# eMMC_SD.net
KiCad netlist of a schematic drawn in Altium Designer
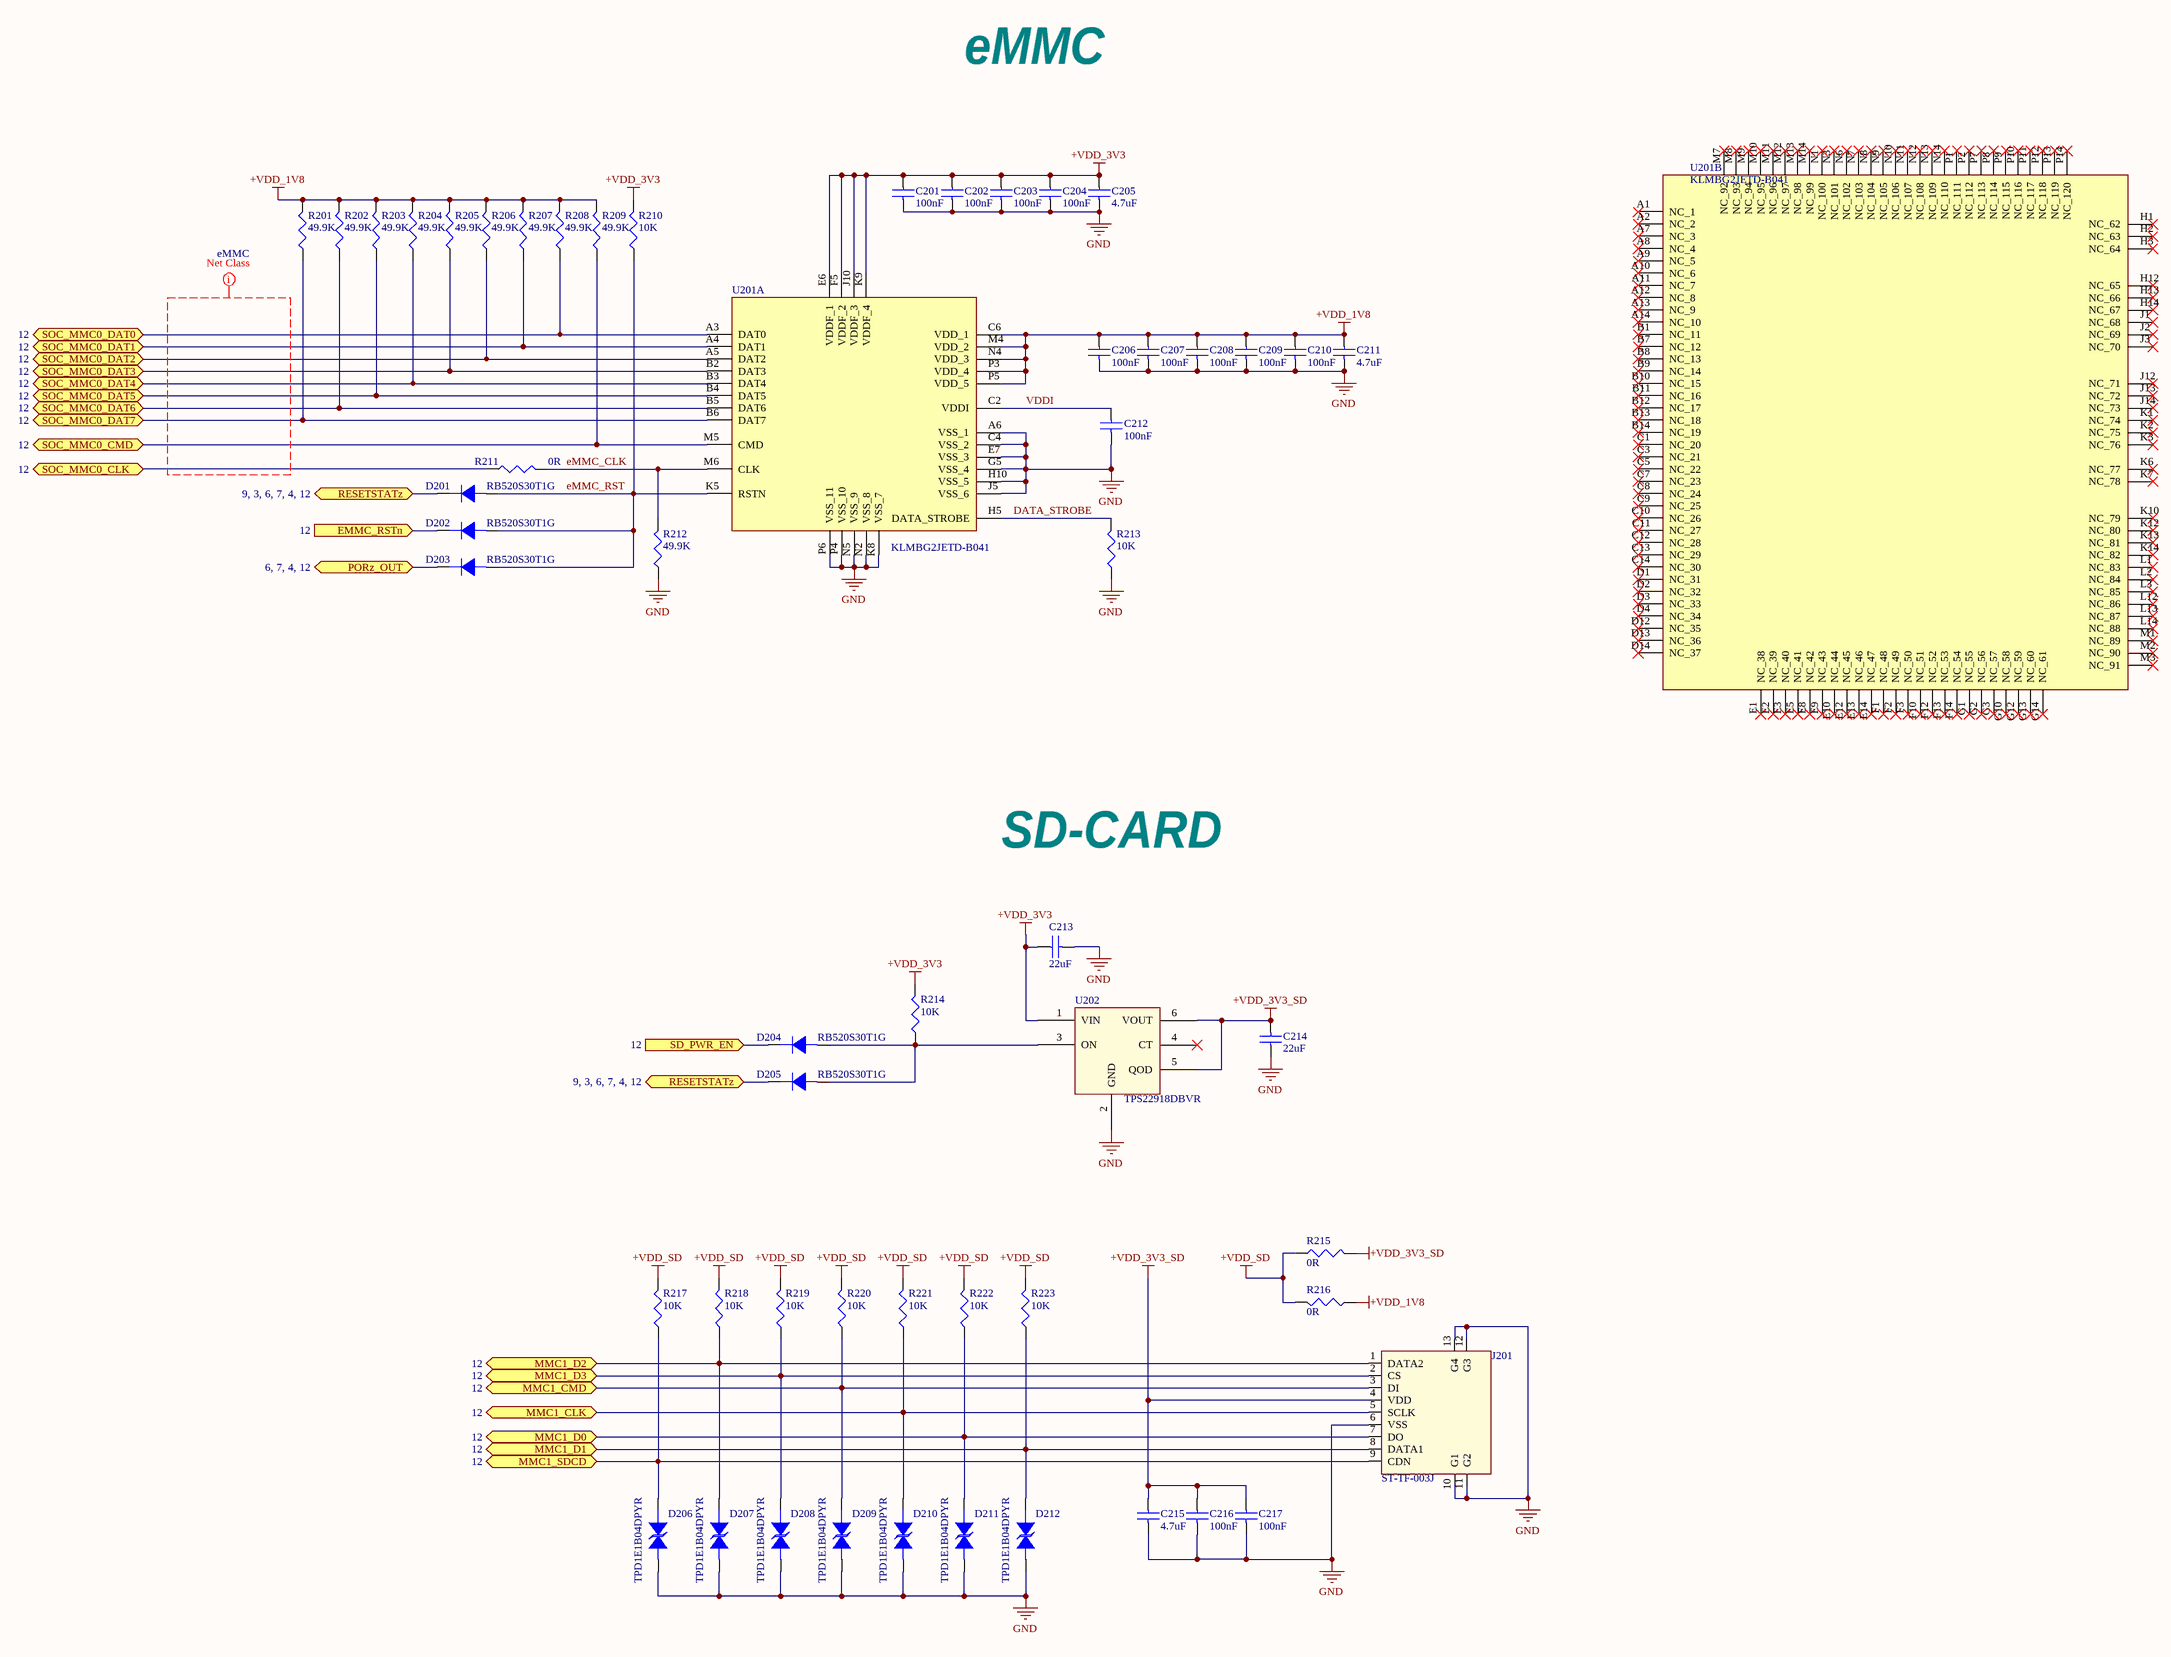
[diagram p0: eMMC&SD.SchDoc]

(export (version "E")
  (design (tool "Eeschema 10.0.6"))
  (components
    (comp (ref "C201")
      (value "100nF")
      (footprint "C0201")
      (description "Multilayer Ceramic Capacitor, 0.1 uF, 16 V, ± 10%, X5R, 0201 [0603 Metric]")
      (fields
        (field (name "MANUFACTURER") "Yageo")
        (field (name "MANUFACTURER PART NUMBER") "CC0201KRX5R6BB104")
      )
      (libsource (lib "Schlib SOM AM625") (part "CC0201KRX5R6BB104"))
    )
    (comp (ref "C202")
      (value "100nF")
      (footprint "C0201")
      (description "Multilayer Ceramic Capacitor, 0.1 uF, 16 V, ± 10%, X5R, 0201 [0603 Metric]")
      (fields
        (field (name "MANUFACTURER") "Yageo")
        (field (name "MANUFACTURER PART NUMBER") "CC0201KRX5R6BB104")
      )
      (libsource (lib "Schlib SOM AM625") (part "CC0201KRX5R6BB104"))
    )
    (comp (ref "C203")
      (value "100nF")
      (footprint "C0201")
      (description "Multilayer Ceramic Capacitor, 0.1 uF, 16 V, ± 10%, X5R, 0201 [0603 Metric]")
      (fields
        (field (name "MANUFACTURER") "Yageo")
        (field (name "MANUFACTURER PART NUMBER") "CC0201KRX5R6BB104")
      )
      (libsource (lib "Schlib SOM AM625") (part "CC0201KRX5R6BB104"))
    )
    (comp (ref "C204")
      (value "100nF")
      (footprint "C0201")
      (description "Multilayer Ceramic Capacitor, 0.1 uF, 16 V, ± 10%, X5R, 0201 [0603 Metric]")
      (fields
        (field (name "MANUFACTURER") "Yageo")
        (field (name "MANUFACTURER PART NUMBER") "CC0201KRX5R6BB104")
      )
      (libsource (lib "Schlib SOM AM625") (part "CC0201KRX5R6BB104"))
    )
    (comp (ref "C205")
      (value "4.7uF")
      (footprint "C0402")
      (description "Multilayer Ceramic Capacitor, 4.7 uF, 6.3V, ± 10%, X5R, 0402 [1005 Metric]")
      (fields
        (field (name "MANUFACTURER") "Yageo")
        (field (name "MANUFACTURER PART NUMBER") "CC0402MRX5R5BB475")
      )
      (libsource (lib "Schlib SOM AM625") (part "CC0402MRX5R5BB475"))
    )
    (comp (ref "C206")
      (value "100nF")
      (footprint "C0201")
      (description "Multilayer Ceramic Capacitor, 0.1 uF, 16 V, ± 10%, X5R, 0201 [0603 Metric]")
      (fields
        (field (name "MANUFACTURER") "Yageo")
        (field (name "MANUFACTURER PART NUMBER") "CC0201KRX5R6BB104")
      )
      (libsource (lib "Schlib SOM AM625") (part "CC0201KRX5R6BB104"))
    )
    (comp (ref "C207")
      (value "100nF")
      (footprint "C0201")
      (description "Multilayer Ceramic Capacitor, 0.1 uF, 16 V, ± 10%, X5R, 0201 [0603 Metric]")
      (fields
        (field (name "MANUFACTURER") "Yageo")
        (field (name "MANUFACTURER PART NUMBER") "CC0201KRX5R6BB104")
      )
      (libsource (lib "Schlib SOM AM625") (part "CC0201KRX5R6BB104"))
    )
    (comp (ref "C208")
      (value "100nF")
      (footprint "C0201")
      (description "Multilayer Ceramic Capacitor, 0.1 uF, 16 V, ± 10%, X5R, 0201 [0603 Metric]")
      (fields
        (field (name "MANUFACTURER") "Yageo")
        (field (name "MANUFACTURER PART NUMBER") "CC0201KRX5R6BB104")
      )
      (libsource (lib "Schlib SOM AM625") (part "CC0201KRX5R6BB104"))
    )
    (comp (ref "C209")
      (value "100nF")
      (footprint "C0201")
      (description "Multilayer Ceramic Capacitor, 0.1 uF, 16 V, ± 10%, X5R, 0201 [0603 Metric]")
      (fields
        (field (name "MANUFACTURER") "Yageo")
        (field (name "MANUFACTURER PART NUMBER") "CC0201KRX5R6BB104")
      )
      (libsource (lib "Schlib SOM AM625") (part "CC0201KRX5R6BB104"))
    )
    (comp (ref "C210")
      (value "100nF")
      (footprint "C0201")
      (description "Multilayer Ceramic Capacitor, 0.1 uF, 16 V, ± 10%, X5R, 0201 [0603 Metric]")
      (fields
        (field (name "MANUFACTURER") "Yageo")
        (field (name "MANUFACTURER PART NUMBER") "CC0201KRX5R6BB104")
      )
      (libsource (lib "Schlib SOM AM625") (part "CC0201KRX5R6BB104"))
    )
    (comp (ref "C211")
      (value "4.7uF")
      (footprint "C0402")
      (description "Multilayer Ceramic Capacitor, 4.7 uF, 6.3V, ± 10%, X5R, 0402 [1005 Metric]")
      (fields
        (field (name "MANUFACTURER") "Yageo")
        (field (name "MANUFACTURER PART NUMBER") "CC0402MRX5R5BB475")
      )
      (libsource (lib "Schlib SOM AM625") (part "CC0402MRX5R5BB475"))
    )
    (comp (ref "C212")
      (value "100nF")
      (footprint "C0201")
      (description "Multilayer Ceramic Capacitor, 0.1 uF, 16 V, ± 10%, X5R, 0201 [0603 Metric]")
      (fields
        (field (name "MANUFACTURER") "Yageo")
        (field (name "MANUFACTURER PART NUMBER") "CC0201KRX5R6BB104")
      )
      (libsource (lib "Schlib SOM AM625") (part "CC0201KRX5R6BB104"))
    )
    (comp (ref "C213")
      (value "22uF")
      (footprint "C0805")
      (description "Multilayer Ceramic Capacitor, 22 uF, 25 V, ± 20%, X6S, 0805 [2012 Metric]")
      (fields
        (field (name "MANUFACTURER") "Yageo")
        (field (name "MANUFACTURER PART NUMBER") "CC0805MKX5R8BB226")
      )
      (libsource (lib "Schlib SOM AM625") (part "CC0805MKX5R8BB226"))
    )
    (comp (ref "C214")
      (value "22uF")
      (footprint "C0805")
      (description "Multilayer Ceramic Capacitor, 22 uF, 25 V, ± 20%, X6S, 0805 [2012 Metric]")
      (fields
        (field (name "MANUFACTURER") "Yageo")
        (field (name "MANUFACTURER PART NUMBER") "CC0805MKX5R8BB226")
      )
      (libsource (lib "Schlib SOM AM625") (part "CC0805MKX5R8BB226"))
    )
    (comp (ref "C215")
      (value "4.7uF")
      (footprint "C0402")
      (description "Multilayer Ceramic Capacitor, 4.7 uF, 6.3V, ± 10%, X5R, 0402 [1005 Metric]")
      (fields
        (field (name "MANUFACTURER") "Yageo")
        (field (name "MANUFACTURER PART NUMBER") "CC0402MRX5R5BB475")
      )
      (libsource (lib "Schlib SOM AM625") (part "CC0402MRX5R5BB475"))
    )
    (comp (ref "C216")
      (value "100nF")
      (footprint "C0201")
      (description "Multilayer Ceramic Capacitor, 0.1 uF, 16 V, ± 10%, X5R, 0201 [0603 Metric]")
      (fields
        (field (name "MANUFACTURER") "Yageo")
        (field (name "MANUFACTURER PART NUMBER") "CC0201KRX5R6BB104")
      )
      (libsource (lib "Schlib SOM AM625") (part "CC0201KRX5R6BB104"))
    )
    (comp (ref "C217")
      (value "100nF")
      (footprint "C0201")
      (description "Multilayer Ceramic Capacitor, 0.1 uF, 16 V, ± 10%, X5R, 0201 [0603 Metric]")
      (fields
        (field (name "MANUFACTURER") "Yageo")
        (field (name "MANUFACTURER PART NUMBER") "CC0201KRX5R6BB104")
      )
      (libsource (lib "Schlib SOM AM625") (part "CC0201KRX5R6BB104"))
    )
    (comp (ref "D201")
      (value "RB520S30T1G")
      (footprint "sod_523")
      (description "Diode Schottky 30V 0.2A 2-Pin SOD-523 T/R - Product that comes on tape, but is not reeled")
      (fields (field (name "MANUFACTURER") "ON Semiconductor"))
      (libsource (lib "Schlib SOM AM625") (part "RB520S30T1G"))
    )
    (comp (ref "D202")
      (value "RB520S30T1G")
      (footprint "sod_523")
      (description "Diode Schottky 30V 0.2A 2-Pin SOD-523 T/R - Product that comes on tape, but is not reeled")
      (fields (field (name "MANUFACTURER") "ON Semiconductor"))
      (libsource (lib "Schlib SOM AM625") (part "RB520S30T1G"))
    )
    (comp (ref "D203")
      (value "RB520S30T1G")
      (footprint "sod_523")
      (description "Diode Schottky 30V 0.2A 2-Pin SOD-523 T/R - Product that comes on tape, but is not reeled")
      (fields (field (name "MANUFACTURER") "ON Semiconductor"))
      (libsource (lib "Schlib SOM AM625") (part "RB520S30T1G"))
    )
    (comp (ref "D204")
      (value "RB520S30T1G")
      (footprint "sod_523")
      (description "Diode Schottky 30V 0.2A 2-Pin SOD-523 T/R - Product that comes on tape, but is not reeled")
      (fields (field (name "MANUFACTURER") "ON Semiconductor"))
      (libsource (lib "Schlib SOM AM625") (part "RB520S30T1G"))
    )
    (comp (ref "D205")
      (value "RB520S30T1G")
      (footprint "sod_523")
      (description "Diode Schottky 30V 0.2A 2-Pin SOD-523 T/R - Product that comes on tape, but is not reeled")
      (fields (field (name "MANUFACTURER") "ON Semiconductor"))
      (libsource (lib "Schlib SOM AM625") (part "RB520S30T1G"))
    )
    (comp (ref "D206")
      (value "TPD1E1B04DPYR")
      (footprint "DIO_TPD1E05U06DPYR")
      (description "1-pF, ±3.6-V, ±30-kV ESD protection diode with 6-A 8/20-uS surge & Low Clamping in 0402 package")
      (fields (field (name "MANUFACTURER") "Texas Instruments"))
      (libsource (lib "Schlib SOM AM625") (part "TPD1E1B04DPYR"))
    )
    (comp (ref "D207")
      (value "TPD1E1B04DPYR")
      (footprint "DIO_TPD1E05U06DPYR")
      (description "1-pF, ±3.6-V, ±30-kV ESD protection diode with 6-A 8/20-uS surge & Low Clamping in 0402 package")
      (fields (field (name "MANUFACTURER") "Texas Instruments"))
      (libsource (lib "Schlib SOM AM625") (part "TPD1E1B04DPYR"))
    )
    (comp (ref "D208")
      (value "TPD1E1B04DPYR")
      (footprint "DIO_TPD1E05U06DPYR")
      (description "1-pF, ±3.6-V, ±30-kV ESD protection diode with 6-A 8/20-uS surge & Low Clamping in 0402 package")
      (fields (field (name "MANUFACTURER") "Texas Instruments"))
      (libsource (lib "Schlib SOM AM625") (part "TPD1E1B04DPYR"))
    )
    (comp (ref "D209")
      (value "TPD1E1B04DPYR")
      (footprint "DIO_TPD1E05U06DPYR")
      (description "1-pF, ±3.6-V, ±30-kV ESD protection diode with 6-A 8/20-uS surge & Low Clamping in 0402 package")
      (fields (field (name "MANUFACTURER") "Texas Instruments"))
      (libsource (lib "Schlib SOM AM625") (part "TPD1E1B04DPYR"))
    )
    (comp (ref "D210")
      (value "TPD1E1B04DPYR")
      (footprint "DIO_TPD1E05U06DPYR")
      (description "1-pF, ±3.6-V, ±30-kV ESD protection diode with 6-A 8/20-uS surge & Low Clamping in 0402 package")
      (fields (field (name "MANUFACTURER") "Texas Instruments"))
      (libsource (lib "Schlib SOM AM625") (part "TPD1E1B04DPYR"))
    )
    (comp (ref "D211")
      (value "TPD1E1B04DPYR")
      (footprint "DIO_TPD1E05U06DPYR")
      (description "1-pF, ±3.6-V, ±30-kV ESD protection diode with 6-A 8/20-uS surge & Low Clamping in 0402 package")
      (fields (field (name "MANUFACTURER") "Texas Instruments"))
      (libsource (lib "Schlib SOM AM625") (part "TPD1E1B04DPYR"))
    )
    (comp (ref "D212")
      (value "TPD1E1B04DPYR")
      (footprint "DIO_TPD1E05U06DPYR")
      (description "1-pF, ±3.6-V, ±30-kV ESD protection diode with 6-A 8/20-uS surge & Low Clamping in 0402 package")
      (fields (field (name "MANUFACTURER") "Texas Instruments"))
      (libsource (lib "Schlib SOM AM625") (part "TPD1E1B04DPYR"))
    )
    (comp (ref "J201")
      (value "ST-TF-003J")
      (footprint "SUNTECH_ST-TF-003A")
      (description "Conn Micro SD Card HDR 8 POS 1.1mm Solder RA SMD Embossed T/R 0.5A")
      (fields (field (name "MANUFACTURER") "Suntech"))
      (libsource (lib "Schlib SOM AM625") (part "ST-TF-003J"))
    )
    (comp (ref "R201")
      (value "49.9K")
      (footprint "R0402")
      (description "SMD Chip Resistor, 49.9 kOhm, ± 1%, 63 mW, 0402 [1005 Metric], Thick Film, General Purpose")
      (fields
        (field (name "MANUFACTURER") "Yageo")
        (field (name "MANUFACTURER PART NUMBER") "RC0402FR-0749K9L")
      )
      (libsource (lib "Schlib SOM AM625") (part "RC0402FR-0749K9L"))
    )
    (comp (ref "R202")
      (value "49.9K")
      (footprint "R0402")
      (description "SMD Chip Resistor, 49.9 kOhm, ± 1%, 63 mW, 0402 [1005 Metric], Thick Film, General Purpose")
      (fields
        (field (name "MANUFACTURER") "Yageo")
        (field (name "MANUFACTURER PART NUMBER") "RC0402FR-0749K9L")
      )
      (libsource (lib "Schlib SOM AM625") (part "RC0402FR-0749K9L"))
    )
    (comp (ref "R203")
      (value "49.9K")
      (footprint "R0402")
      (description "SMD Chip Resistor, 49.9 kOhm, ± 1%, 63 mW, 0402 [1005 Metric], Thick Film, General Purpose")
      (fields
        (field (name "MANUFACTURER") "Yageo")
        (field (name "MANUFACTURER PART NUMBER") "RC0402FR-0749K9L")
      )
      (libsource (lib "Schlib SOM AM625") (part "RC0402FR-0749K9L"))
    )
    (comp (ref "R204")
      (value "49.9K")
      (footprint "R0402")
      (description "SMD Chip Resistor, 49.9 kOhm, ± 1%, 63 mW, 0402 [1005 Metric], Thick Film, General Purpose")
      (fields
        (field (name "MANUFACTURER") "Yageo")
        (field (name "MANUFACTURER PART NUMBER") "RC0402FR-0749K9L")
      )
      (libsource (lib "Schlib SOM AM625") (part "RC0402FR-0749K9L"))
    )
    (comp (ref "R205")
      (value "49.9K")
      (footprint "R0402")
      (description "SMD Chip Resistor, 49.9 kOhm, ± 1%, 63 mW, 0402 [1005 Metric], Thick Film, General Purpose")
      (fields
        (field (name "MANUFACTURER") "Yageo")
        (field (name "MANUFACTURER PART NUMBER") "RC0402FR-0749K9L")
      )
      (libsource (lib "Schlib SOM AM625") (part "RC0402FR-0749K9L"))
    )
    (comp (ref "R206")
      (value "49.9K")
      (footprint "R0402")
      (description "SMD Chip Resistor, 49.9 kOhm, ± 1%, 63 mW, 0402 [1005 Metric], Thick Film, General Purpose")
      (fields
        (field (name "MANUFACTURER") "Yageo")
        (field (name "MANUFACTURER PART NUMBER") "RC0402FR-0749K9L")
      )
      (libsource (lib "Schlib SOM AM625") (part "RC0402FR-0749K9L"))
    )
    (comp (ref "R207")
      (value "49.9K")
      (footprint "R0402")
      (description "SMD Chip Resistor, 49.9 kOhm, ± 1%, 63 mW, 0402 [1005 Metric], Thick Film, General Purpose")
      (fields
        (field (name "MANUFACTURER") "Yageo")
        (field (name "MANUFACTURER PART NUMBER") "RC0402FR-0749K9L")
      )
      (libsource (lib "Schlib SOM AM625") (part "RC0402FR-0749K9L"))
    )
    (comp (ref "R208")
      (value "49.9K")
      (footprint "R0402")
      (description "SMD Chip Resistor, 49.9 kOhm, ± 1%, 63 mW, 0402 [1005 Metric], Thick Film, General Purpose")
      (fields
        (field (name "MANUFACTURER") "Yageo")
        (field (name "MANUFACTURER PART NUMBER") "RC0402FR-0749K9L")
      )
      (libsource (lib "Schlib SOM AM625") (part "RC0402FR-0749K9L"))
    )
    (comp (ref "R209")
      (value "49.9K")
      (footprint "R0402")
      (description "SMD Chip Resistor, 49.9 kOhm, ± 1%, 63 mW, 0402 [1005 Metric], Thick Film, General Purpose")
      (fields
        (field (name "MANUFACTURER") "Yageo")
        (field (name "MANUFACTURER PART NUMBER") "RC0402FR-0749K9L")
      )
      (libsource (lib "Schlib SOM AM625") (part "RC0402FR-0749K9L"))
    )
    (comp (ref "R210")
      (value "10K")
      (footprint "R0402")
      (description "RES 10.0K OHM 1/16W 1% 0402 SMD")
      (fields
        (field (name "MANUFACTURER") "Yageo")
        (field (name "MANUFACTURER PART NUMBER") "RC0402FR-0710KL")
      )
      (libsource (lib "Schlib SOM AM625") (part "RC0402FR-0710KL"))
    )
    (comp (ref "R211")
      (value "0R")
      (footprint "R0402")
      (description "Zero Ohm Resistor, Jumper, 0402 [1005 Metric], Thick Film, 63 mW, 1 A, Surface Mount")
      (fields
        (field (name "MANUFACTURER") "Yageo")
        (field (name "MANUFACTURER PART NUMBER") "RC0402JR-070RL")
      )
      (libsource (lib "Schlib SOM AM625") (part "RC0402JR-070RL"))
    )
    (comp (ref "R212")
      (value "49.9K")
      (footprint "R0402")
      (description "SMD Chip Resistor, 49.9 kOhm, ± 1%, 63 mW, 0402 [1005 Metric], Thick Film, General Purpose")
      (fields
        (field (name "MANUFACTURER") "Yageo")
        (field (name "MANUFACTURER PART NUMBER") "RC0402FR-0749K9L")
      )
      (libsource (lib "Schlib SOM AM625") (part "RC0402FR-0749K9L"))
    )
    (comp (ref "R213")
      (value "10K")
      (footprint "R0402")
      (description "RES 10.0K OHM 1/16W 1% 0402 SMD")
      (fields
        (field (name "MANUFACTURER") "Yageo")
        (field (name "MANUFACTURER PART NUMBER") "RC0402FR-0710KL")
      )
      (libsource (lib "Schlib SOM AM625") (part "RC0402FR-0710KL"))
    )
    (comp (ref "R214")
      (value "10K")
      (footprint "R0402")
      (description "RES 10.0K OHM 1/16W 1% 0402 SMD")
      (fields
        (field (name "MANUFACTURER") "Yageo")
        (field (name "MANUFACTURER PART NUMBER") "RC0402FR-0710KL")
      )
      (libsource (lib "Schlib SOM AM625") (part "RC0402FR-0710KL"))
    )
    (comp (ref "R215")
      (value "0R")
      (footprint "R0402")
      (description "Zero Ohm Resistor, Jumper, 0402 [1005 Metric], Thick Film, 63 mW, 1 A, Surface Mount")
      (fields
        (field (name "MANUFACTURER") "Yageo")
        (field (name "MANUFACTURER PART NUMBER") "RC0402JR-070RL")
      )
      (libsource (lib "Schlib SOM AM625") (part "RC0402JR-070RL"))
    )
    (comp (ref "R216")
      (value "0R")
      (footprint "R0402")
      (description "Zero Ohm Resistor, Jumper, 0402 [1005 Metric], Thick Film, 63 mW, 1 A, Surface Mount")
      (fields
        (field (name "MANUFACTURER") "Yageo")
        (field (name "MANUFACTURER PART NUMBER") "RC0402JR-070RL")
      )
      (libsource (lib "Schlib SOM AM625") (part "RC0402JR-070RL"))
    )
    (comp (ref "R217")
      (value "10K")
      (footprint "R0402")
      (description "RES 10.0K OHM 1/16W 1% 0402 SMD")
      (fields
        (field (name "MANUFACTURER") "Yageo")
        (field (name "MANUFACTURER PART NUMBER") "RC0402FR-0710KL")
      )
      (libsource (lib "Schlib SOM AM625") (part "RC0402FR-0710KL"))
    )
    (comp (ref "R218")
      (value "10K")
      (footprint "R0402")
      (description "RES 10.0K OHM 1/16W 1% 0402 SMD")
      (fields
        (field (name "MANUFACTURER") "Yageo")
        (field (name "MANUFACTURER PART NUMBER") "RC0402FR-0710KL")
      )
      (libsource (lib "Schlib SOM AM625") (part "RC0402FR-0710KL"))
    )
    (comp (ref "R219")
      (value "10K")
      (footprint "R0402")
      (description "RES 10.0K OHM 1/16W 1% 0402 SMD")
      (fields
        (field (name "MANUFACTURER") "Yageo")
        (field (name "MANUFACTURER PART NUMBER") "RC0402FR-0710KL")
      )
      (libsource (lib "Schlib SOM AM625") (part "RC0402FR-0710KL"))
    )
    (comp (ref "R220")
      (value "10K")
      (footprint "R0402")
      (description "RES 10.0K OHM 1/16W 1% 0402 SMD")
      (fields
        (field (name "MANUFACTURER") "Yageo")
        (field (name "MANUFACTURER PART NUMBER") "RC0402FR-0710KL")
      )
      (libsource (lib "Schlib SOM AM625") (part "RC0402FR-0710KL"))
    )
    (comp (ref "R221")
      (value "10K")
      (footprint "R0402")
      (description "RES 10.0K OHM 1/16W 1% 0402 SMD")
      (fields
        (field (name "MANUFACTURER") "Yageo")
        (field (name "MANUFACTURER PART NUMBER") "RC0402FR-0710KL")
      )
      (libsource (lib "Schlib SOM AM625") (part "RC0402FR-0710KL"))
    )
    (comp (ref "R222")
      (value "10K")
      (footprint "R0402")
      (description "RES 10.0K OHM 1/16W 1% 0402 SMD")
      (fields
        (field (name "MANUFACTURER") "Yageo")
        (field (name "MANUFACTURER PART NUMBER") "RC0402FR-0710KL")
      )
      (libsource (lib "Schlib SOM AM625") (part "RC0402FR-0710KL"))
    )
    (comp (ref "R223")
      (value "10K")
      (footprint "R0402")
      (description "RES 10.0K OHM 1/16W 1% 0402 SMD")
      (fields
        (field (name "MANUFACTURER") "Yageo")
        (field (name "MANUFACTURER PART NUMBER") "RC0402FR-0710KL")
      )
      (libsource (lib "Schlib SOM AM625") (part "RC0402FR-0710KL"))
    )
    (comp (ref "U201")
      (value "KLMBG2JETD-B041")
      (footprint "BGA153C50P14X14_1150X1300X80")
      (description "eMMC 5.1 BGA-153 eMMC ROHS")
      (libsource (lib "Schlib1") (part "KLMAG1JETD-B041"))
    )
    (comp (ref "U202")
      (value "TPS22918DBVR")
      (footprint "SOT23-6")
      (description "IC SINGLE CHANNEL LOAD SWITCH")
      (fields (field (name "MANUFACTURER") "Texas Instruments"))
      (libsource (lib "Schlib SOM AM625") (part "TPS22918DBVR"))
    )
  )
  (nets
    (net (code "1") (name "+VDD_1V8") (class "Default")
      (node (ref "C206") (pin "1") (pinfunction "1_1") (pintype "passive"))
      (node (ref "C207") (pin "1") (pinfunction "1_1") (pintype "passive"))
      (node (ref "C208") (pin "1") (pinfunction "1_1") (pintype "passive"))
      (node (ref "C209") (pin "1") (pinfunction "1_1") (pintype "passive"))
      (node (ref "C210") (pin "1") (pinfunction "1_1") (pintype "passive"))
      (node (ref "C211") (pin "1") (pinfunction "1_1") (pintype "passive"))
      (node (ref "R201") (pin "2") (pinfunction "2_2") (pintype "passive"))
      (node (ref "R202") (pin "2") (pinfunction "2_2") (pintype "passive"))
      (node (ref "R203") (pin "2") (pinfunction "2_2") (pintype "passive"))
      (node (ref "R204") (pin "2") (pinfunction "2_2") (pintype "passive"))
      (node (ref "R205") (pin "2") (pinfunction "2_2") (pintype "passive"))
      (node (ref "R206") (pin "2") (pinfunction "2_2") (pintype "passive"))
      (node (ref "R207") (pin "2") (pinfunction "2_2") (pintype "passive"))
      (node (ref "R208") (pin "2") (pinfunction "2_2") (pintype "passive"))
      (node (ref "R209") (pin "2") (pinfunction "2_2") (pintype "passive"))
      (node (ref "R216") (pin "1") (pinfunction "1_1") (pintype "passive"))
      (node (ref "U201") (pin "C6") (pinfunction "VDD_1_C6") (pintype "passive"))
      (node (ref "U201") (pin "M4") (pinfunction "VDD_2_M4") (pintype "passive"))
      (node (ref "U201") (pin "N4") (pinfunction "VDD_3_N4") (pintype "passive"))
      (node (ref "U201") (pin "P3") (pinfunction "VDD_4_P3") (pintype "passive"))
      (node (ref "U201") (pin "P5") (pinfunction "VDD_5_P5") (pintype "passive"))
    )
    (net (code "2") (name "+VDD_3V3") (class "Default")
      (node (ref "C201") (pin "1") (pinfunction "1_1") (pintype "passive"))
      (node (ref "C202") (pin "1") (pinfunction "1_1") (pintype "passive"))
      (node (ref "C203") (pin "1") (pinfunction "1_1") (pintype "passive"))
      (node (ref "C204") (pin "1") (pinfunction "1_1") (pintype "passive"))
      (node (ref "C205") (pin "1") (pinfunction "1_1") (pintype "passive"))
      (node (ref "C213") (pin "1") (pinfunction "1_1") (pintype "passive"))
      (node (ref "R210") (pin "2") (pinfunction "2_2") (pintype "passive"))
      (node (ref "R214") (pin "2") (pinfunction "2_2") (pintype "passive"))
      (node (ref "U201") (pin "E6") (pinfunction "VDDF_1_E6") (pintype "passive"))
      (node (ref "U201") (pin "F5") (pinfunction "VDDF_2_F5") (pintype "passive"))
      (node (ref "U201") (pin "J10") (pinfunction "VDDF_3_J10") (pintype "passive"))
      (node (ref "U201") (pin "K9") (pinfunction "VDDF_4_K9") (pintype "passive"))
      (node (ref "U202") (pin "1") (pinfunction "VIN_1") (pintype "passive"))
    )
    (net (code "3") (name "+VDD_3V3_SD") (class "Default")
      (node (ref "C214") (pin "2") (pinfunction "2_2") (pintype "passive"))
      (node (ref "C215") (pin "1") (pinfunction "1_1") (pintype "passive"))
      (node (ref "C216") (pin "1") (pinfunction "1_1") (pintype "passive"))
      (node (ref "C217") (pin "1") (pinfunction "1_1") (pintype "passive"))
      (node (ref "J201") (pin "4") (pinfunction "VDD_4") (pintype "passive"))
      (node (ref "R215") (pin "2") (pinfunction "2_2") (pintype "passive"))
      (node (ref "U202") (pin "5") (pinfunction "QOD_5") (pintype "passive"))
      (node (ref "U202") (pin "6") (pinfunction "VOUT_6") (pintype "passive"))
    )
    (net (code "4") (name "+VDD_SD") (class "Default")
      (node (ref "R215") (pin "1") (pinfunction "1_1") (pintype "passive"))
      (node (ref "R216") (pin "2") (pinfunction "2_2") (pintype "passive"))
      (node (ref "R217") (pin "2") (pinfunction "2_2") (pintype "passive"))
      (node (ref "R218") (pin "2") (pinfunction "2_2") (pintype "passive"))
      (node (ref "R219") (pin "2") (pinfunction "2_2") (pintype "passive"))
      (node (ref "R220") (pin "2") (pinfunction "2_2") (pintype "passive"))
      (node (ref "R221") (pin "2") (pinfunction "2_2") (pintype "passive"))
      (node (ref "R222") (pin "2") (pinfunction "2_2") (pintype "passive"))
      (node (ref "R223") (pin "2") (pinfunction "2_2") (pintype "passive"))
    )
    (net (code "5") (name "/DATA_STROBE") (class "Default")
      (node (ref "R213") (pin "2") (pinfunction "2_2") (pintype "passive"))
      (node (ref "U201") (pin "H5") (pinfunction "DATA_STROBE_H5") (pintype "passive"))
    )
    (net (code "6") (name "/EMMC_RSTn") (class "Default")
      (node (ref "D202") (pin "2") (pinfunction "C_2") (pintype "passive"))
    )
    (net (code "7") (name "/MMC1_CLK") (class "Default")
      (node (ref "D210") (pin "2") (pinfunction "2_2") (pintype "passive"))
      (node (ref "J201") (pin "5") (pinfunction "SCLK_5") (pintype "passive"))
      (node (ref "R221") (pin "1") (pinfunction "1_1") (pintype "passive"))
    )
    (net (code "8") (name "/MMC1_CMD") (class "Default")
      (node (ref "D209") (pin "2") (pinfunction "2_2") (pintype "passive"))
      (node (ref "J201") (pin "3") (pinfunction "DI_3") (pintype "passive"))
      (node (ref "R220") (pin "1") (pinfunction "1_1") (pintype "passive"))
    )
    (net (code "9") (name "/MMC1_D0") (class "Default")
      (node (ref "D211") (pin "2") (pinfunction "2_2") (pintype "passive"))
      (node (ref "J201") (pin "7") (pinfunction "DO_7") (pintype "passive"))
      (node (ref "R222") (pin "1") (pinfunction "1_1") (pintype "passive"))
    )
    (net (code "10") (name "/MMC1_D1") (class "Default")
      (node (ref "D212") (pin "2") (pinfunction "2_2") (pintype "passive"))
      (node (ref "J201") (pin "8") (pinfunction "DATA1_8") (pintype "passive"))
      (node (ref "R223") (pin "1") (pinfunction "1_1") (pintype "passive"))
    )
    (net (code "11") (name "/MMC1_D2") (class "Default")
      (node (ref "D207") (pin "2") (pinfunction "2_2") (pintype "passive"))
      (node (ref "J201") (pin "1") (pinfunction "DATA2_1") (pintype "passive"))
      (node (ref "R218") (pin "1") (pinfunction "1_1") (pintype "passive"))
    )
    (net (code "12") (name "/MMC1_D3") (class "Default")
      (node (ref "D208") (pin "2") (pinfunction "2_2") (pintype "passive"))
      (node (ref "J201") (pin "2") (pinfunction "CS_2") (pintype "passive"))
      (node (ref "R219") (pin "1") (pinfunction "1_1") (pintype "passive"))
    )
    (net (code "13") (name "/MMC1_SDCD") (class "Default")
      (node (ref "D206") (pin "2") (pinfunction "2_2") (pintype "passive"))
      (node (ref "J201") (pin "9") (pinfunction "CDN_9") (pintype "passive"))
      (node (ref "R217") (pin "1") (pinfunction "1_1") (pintype "passive"))
    )
    (net (code "14") (name "/PORz_OUT") (class "Default")
      (node (ref "D203") (pin "2") (pinfunction "C_2") (pintype "passive"))
    )
    (net (code "15") (name "/RESETSTATz") (class "Default")
      (node (ref "D201") (pin "2") (pinfunction "C_2") (pintype "passive"))
      (node (ref "D205") (pin "2") (pinfunction "C_2") (pintype "passive"))
    )
    (net (code "16") (name "/SD_PWR_EN") (class "Default")
      (node (ref "D204") (pin "2") (pinfunction "C_2") (pintype "passive"))
    )
    (net (code "17") (name "/SOC_MMC0_CLK") (class "Default")
      (node (ref "R211") (pin "1") (pinfunction "1_1") (pintype "passive"))
    )
    (net (code "18") (name "/SOC_MMC0_CMD") (class "Default")
      (node (ref "R209") (pin "1") (pinfunction "1_1") (pintype "passive"))
      (node (ref "U201") (pin "M5") (pinfunction "CMD_M5") (pintype "passive"))
    )
    (net (code "19") (name "/SOC_MMC0_DAT0") (class "Default")
      (node (ref "R208") (pin "1") (pinfunction "1_1") (pintype "passive"))
      (node (ref "U201") (pin "A3") (pinfunction "DAT0_A3") (pintype "passive"))
    )
    (net (code "20") (name "/SOC_MMC0_DAT1") (class "Default")
      (node (ref "R207") (pin "1") (pinfunction "1_1") (pintype "passive"))
      (node (ref "U201") (pin "A4") (pinfunction "DAT1_A4") (pintype "passive"))
    )
    (net (code "21") (name "/SOC_MMC0_DAT2") (class "Default")
      (node (ref "R206") (pin "1") (pinfunction "1_1") (pintype "passive"))
      (node (ref "U201") (pin "A5") (pinfunction "DAT2_A5") (pintype "passive"))
    )
    (net (code "22") (name "/SOC_MMC0_DAT3") (class "Default")
      (node (ref "R205") (pin "1") (pinfunction "1_1") (pintype "passive"))
      (node (ref "U201") (pin "B2") (pinfunction "DAT3_B2") (pintype "passive"))
    )
    (net (code "23") (name "/SOC_MMC0_DAT4") (class "Default")
      (node (ref "R204") (pin "1") (pinfunction "1_1") (pintype "passive"))
      (node (ref "U201") (pin "B3") (pinfunction "DAT4_B3") (pintype "passive"))
    )
    (net (code "24") (name "/SOC_MMC0_DAT5") (class "Default")
      (node (ref "R203") (pin "1") (pinfunction "1_1") (pintype "passive"))
      (node (ref "U201") (pin "B4") (pinfunction "DAT5_B4") (pintype "passive"))
    )
    (net (code "25") (name "/SOC_MMC0_DAT6") (class "Default")
      (node (ref "R202") (pin "1") (pinfunction "1_1") (pintype "passive"))
      (node (ref "U201") (pin "B5") (pinfunction "DAT6_B5") (pintype "passive"))
    )
    (net (code "26") (name "/SOC_MMC0_DAT7") (class "Default")
      (node (ref "R201") (pin "1") (pinfunction "1_1") (pintype "passive"))
      (node (ref "U201") (pin "B6") (pinfunction "DAT7_B6") (pintype "passive"))
    )
    (net (code "27") (name "/VDDI") (class "Default")
      (node (ref "C212") (pin "1") (pinfunction "1_1") (pintype "passive"))
      (node (ref "U201") (pin "C2") (pinfunction "VDDI_C2") (pintype "passive"))
    )
    (net (code "28") (name "/eMMC_CLK") (class "Default")
      (node (ref "R211") (pin "2") (pinfunction "2_2") (pintype "passive"))
      (node (ref "R212") (pin "2") (pinfunction "2_2") (pintype "passive"))
      (node (ref "U201") (pin "M6") (pinfunction "CLK_M6") (pintype "passive"))
    )
    (net (code "29") (name "/eMMC_RST") (class "Default")
      (node (ref "D201") (pin "1") (pinfunction "A_1") (pintype "passive"))
      (node (ref "D202") (pin "1") (pinfunction "A_1") (pintype "passive"))
      (node (ref "D203") (pin "1") (pinfunction "A_1") (pintype "passive"))
      (node (ref "R210") (pin "1") (pinfunction "1_1") (pintype "passive"))
      (node (ref "U201") (pin "K5") (pinfunction "RSTN_K5") (pintype "passive"))
    )
    (net (code "30") (name "GND") (class "Default")
      (node (ref "C201") (pin "2") (pinfunction "2_2") (pintype "passive"))
      (node (ref "C202") (pin "2") (pinfunction "2_2") (pintype "passive"))
      (node (ref "C203") (pin "2") (pinfunction "2_2") (pintype "passive"))
      (node (ref "C204") (pin "2") (pinfunction "2_2") (pintype "passive"))
      (node (ref "C205") (pin "2") (pinfunction "2_2") (pintype "passive"))
      (node (ref "C206") (pin "2") (pinfunction "2_2") (pintype "passive"))
      (node (ref "C207") (pin "2") (pinfunction "2_2") (pintype "passive"))
      (node (ref "C208") (pin "2") (pinfunction "2_2") (pintype "passive"))
      (node (ref "C209") (pin "2") (pinfunction "2_2") (pintype "passive"))
      (node (ref "C210") (pin "2") (pinfunction "2_2") (pintype "passive"))
      (node (ref "C211") (pin "2") (pinfunction "2_2") (pintype "passive"))
      (node (ref "C212") (pin "2") (pinfunction "2_2") (pintype "passive"))
      (node (ref "C213") (pin "2") (pinfunction "2_2") (pintype "passive"))
      (node (ref "C214") (pin "1") (pinfunction "1_1") (pintype "passive"))
      (node (ref "C215") (pin "2") (pinfunction "2_2") (pintype "passive"))
      (node (ref "C216") (pin "2") (pinfunction "2_2") (pintype "passive"))
      (node (ref "C217") (pin "2") (pinfunction "2_2") (pintype "passive"))
      (node (ref "D206") (pin "1") (pinfunction "1_1") (pintype "passive"))
      (node (ref "D207") (pin "1") (pinfunction "1_1") (pintype "passive"))
      (node (ref "D208") (pin "1") (pinfunction "1_1") (pintype "passive"))
      (node (ref "D209") (pin "1") (pinfunction "1_1") (pintype "passive"))
      (node (ref "D210") (pin "1") (pinfunction "1_1") (pintype "passive"))
      (node (ref "D211") (pin "1") (pinfunction "1_1") (pintype "passive"))
      (node (ref "D212") (pin "1") (pinfunction "1_1") (pintype "passive"))
      (node (ref "J201") (pin "10") (pinfunction "G1_10") (pintype "passive"))
      (node (ref "J201") (pin "11") (pinfunction "G2_11") (pintype "passive"))
      (node (ref "J201") (pin "12") (pinfunction "G3_12") (pintype "passive"))
      (node (ref "J201") (pin "13") (pinfunction "G4_13") (pintype "passive"))
      (node (ref "J201") (pin "6") (pinfunction "VSS_6") (pintype "passive"))
      (node (ref "R212") (pin "1") (pinfunction "1_1") (pintype "passive"))
      (node (ref "R213") (pin "1") (pinfunction "1_1") (pintype "passive"))
      (node (ref "U201") (pin "A6") (pinfunction "VSS_1_A6") (pintype "passive"))
      (node (ref "U201") (pin "C4") (pinfunction "VSS_2_C4") (pintype "passive"))
      (node (ref "U201") (pin "E7") (pinfunction "VSS_3_E7") (pintype "passive"))
      (node (ref "U201") (pin "G5") (pinfunction "VSS_4_G5") (pintype "passive"))
      (node (ref "U201") (pin "H10") (pinfunction "VSS_5_H10") (pintype "passive"))
      (node (ref "U201") (pin "J5") (pinfunction "VSS_6_J5") (pintype "passive"))
      (node (ref "U201") (pin "K8") (pinfunction "VSS_7_K8") (pintype "passive"))
      (node (ref "U201") (pin "N2") (pinfunction "VSS_8_N2") (pintype "passive"))
      (node (ref "U201") (pin "N5") (pinfunction "VSS_9_N5") (pintype "passive"))
      (node (ref "U201") (pin "P4") (pinfunction "VSS_10_P4") (pintype "passive"))
      (node (ref "U201") (pin "P6") (pinfunction "VSS_11_P6") (pintype "passive"))
      (node (ref "U202") (pin "2") (pinfunction "GND_2") (pintype "power_in"))
    )
    (net (code "31") (name "Net-(D204-A)") (class "Default")
      (node (ref "D204") (pin "1") (pinfunction "A_1") (pintype "passive"))
      (node (ref "D205") (pin "1") (pinfunction "A_1") (pintype "passive"))
      (node (ref "R214") (pin "1") (pinfunction "1_1") (pintype "passive"))
      (node (ref "U202") (pin "3") (pinfunction "ON_3") (pintype "passive"))
    )
    (net (code "32") (name "unconnected-(U201B-NC_1-PadA1)") (class "Default")
      (node (ref "U201") (pin "A1") (pinfunction "NC_1_A1") (pintype "passive+no_connect"))
    )
    (net (code "33") (name "unconnected-(U201B-NC_2-PadA2)") (class "Default")
      (node (ref "U201") (pin "A2") (pinfunction "NC_2_A2") (pintype "passive+no_connect"))
    )
    (net (code "34") (name "unconnected-(U201B-NC_3-PadA7)") (class "Default")
      (node (ref "U201") (pin "A7") (pinfunction "NC_3_A7") (pintype "passive+no_connect"))
    )
    (net (code "35") (name "unconnected-(U201B-NC_4-PadA8)") (class "Default")
      (node (ref "U201") (pin "A8") (pinfunction "NC_4_A8") (pintype "passive+no_connect"))
    )
    (net (code "36") (name "unconnected-(U201B-NC_5-PadA9)") (class "Default")
      (node (ref "U201") (pin "A9") (pinfunction "NC_5_A9") (pintype "passive+no_connect"))
    )
    (net (code "37") (name "unconnected-(U201B-NC_6-PadA10)") (class "Default")
      (node (ref "U201") (pin "A10") (pinfunction "NC_6_A10") (pintype "passive+no_connect"))
    )
    (net (code "38") (name "unconnected-(U201B-NC_7-PadA11)") (class "Default")
      (node (ref "U201") (pin "A11") (pinfunction "NC_7_A11") (pintype "passive+no_connect"))
    )
    (net (code "39") (name "unconnected-(U201B-NC_8-PadA12)") (class "Default")
      (node (ref "U201") (pin "A12") (pinfunction "NC_8_A12") (pintype "passive+no_connect"))
    )
    (net (code "40") (name "unconnected-(U201B-NC_9-PadA13)") (class "Default")
      (node (ref "U201") (pin "A13") (pinfunction "NC_9_A13") (pintype "passive+no_connect"))
    )
    (net (code "41") (name "unconnected-(U201B-NC_10-PadA14)") (class "Default")
      (node (ref "U201") (pin "A14") (pinfunction "NC_10_A14") (pintype "passive+no_connect"))
    )
    (net (code "42") (name "unconnected-(U201B-NC_11-PadB1)") (class "Default")
      (node (ref "U201") (pin "B1") (pinfunction "NC_11_B1") (pintype "passive+no_connect"))
    )
    (net (code "43") (name "unconnected-(U201B-NC_12-PadB7)") (class "Default")
      (node (ref "U201") (pin "B7") (pinfunction "NC_12_B7") (pintype "passive+no_connect"))
    )
    (net (code "44") (name "unconnected-(U201B-NC_13-PadB8)") (class "Default")
      (node (ref "U201") (pin "B8") (pinfunction "NC_13_B8") (pintype "passive+no_connect"))
    )
    (net (code "45") (name "unconnected-(U201B-NC_14-PadB9)") (class "Default")
      (node (ref "U201") (pin "B9") (pinfunction "NC_14_B9") (pintype "passive+no_connect"))
    )
    (net (code "46") (name "unconnected-(U201B-NC_15-PadB10)") (class "Default")
      (node (ref "U201") (pin "B10") (pinfunction "NC_15_B10") (pintype "passive+no_connect"))
    )
    (net (code "47") (name "unconnected-(U201B-NC_16-PadB11)") (class "Default")
      (node (ref "U201") (pin "B11") (pinfunction "NC_16_B11") (pintype "passive+no_connect"))
    )
    (net (code "48") (name "unconnected-(U201B-NC_17-PadB12)") (class "Default")
      (node (ref "U201") (pin "B12") (pinfunction "NC_17_B12") (pintype "passive+no_connect"))
    )
    (net (code "49") (name "unconnected-(U201B-NC_18-PadB13)") (class "Default")
      (node (ref "U201") (pin "B13") (pinfunction "NC_18_B13") (pintype "passive+no_connect"))
    )
    (net (code "50") (name "unconnected-(U201B-NC_19-PadB14)") (class "Default")
      (node (ref "U201") (pin "B14") (pinfunction "NC_19_B14") (pintype "passive+no_connect"))
    )
    (net (code "51") (name "unconnected-(U201B-NC_20-PadC1)") (class "Default")
      (node (ref "U201") (pin "C1") (pinfunction "NC_20_C1") (pintype "passive+no_connect"))
    )
    (net (code "52") (name "unconnected-(U201B-NC_21-PadC3)") (class "Default")
      (node (ref "U201") (pin "C3") (pinfunction "NC_21_C3") (pintype "passive+no_connect"))
    )
    (net (code "53") (name "unconnected-(U201B-NC_22-PadC5)") (class "Default")
      (node (ref "U201") (pin "C5") (pinfunction "NC_22_C5") (pintype "passive+no_connect"))
    )
    (net (code "54") (name "unconnected-(U201B-NC_23-PadC7)") (class "Default")
      (node (ref "U201") (pin "C7") (pinfunction "NC_23_C7") (pintype "passive+no_connect"))
    )
    (net (code "55") (name "unconnected-(U201B-NC_24-PadC8)") (class "Default")
      (node (ref "U201") (pin "C8") (pinfunction "NC_24_C8") (pintype "passive+no_connect"))
    )
    (net (code "56") (name "unconnected-(U201B-NC_25-PadC9)") (class "Default")
      (node (ref "U201") (pin "C9") (pinfunction "NC_25_C9") (pintype "passive+no_connect"))
    )
    (net (code "57") (name "unconnected-(U201B-NC_26-PadC10)") (class "Default")
      (node (ref "U201") (pin "C10") (pinfunction "NC_26_C10") (pintype "passive+no_connect"))
    )
    (net (code "58") (name "unconnected-(U201B-NC_27-PadC11)") (class "Default")
      (node (ref "U201") (pin "C11") (pinfunction "NC_27_C11") (pintype "passive+no_connect"))
    )
    (net (code "59") (name "unconnected-(U201B-NC_28-PadC12)") (class "Default")
      (node (ref "U201") (pin "C12") (pinfunction "NC_28_C12") (pintype "passive+no_connect"))
    )
    (net (code "60") (name "unconnected-(U201B-NC_29-PadC13)") (class "Default")
      (node (ref "U201") (pin "C13") (pinfunction "NC_29_C13") (pintype "passive+no_connect"))
    )
    (net (code "61") (name "unconnected-(U201B-NC_30-PadC14)") (class "Default")
      (node (ref "U201") (pin "C14") (pinfunction "NC_30_C14") (pintype "passive+no_connect"))
    )
    (net (code "62") (name "unconnected-(U201B-NC_31-PadD1)") (class "Default")
      (node (ref "U201") (pin "D1") (pinfunction "NC_31_D1") (pintype "passive+no_connect"))
    )
    (net (code "63") (name "unconnected-(U201B-NC_32-PadD2)") (class "Default")
      (node (ref "U201") (pin "D2") (pinfunction "NC_32_D2") (pintype "passive+no_connect"))
    )
    (net (code "64") (name "unconnected-(U201B-NC_33-PadD3)") (class "Default")
      (node (ref "U201") (pin "D3") (pinfunction "NC_33_D3") (pintype "passive+no_connect"))
    )
    (net (code "65") (name "unconnected-(U201B-NC_34-PadD4)") (class "Default")
      (node (ref "U201") (pin "D4") (pinfunction "NC_34_D4") (pintype "passive+no_connect"))
    )
    (net (code "66") (name "unconnected-(U201B-NC_35-PadD12)") (class "Default")
      (node (ref "U201") (pin "D12") (pinfunction "NC_35_D12") (pintype "passive+no_connect"))
    )
    (net (code "67") (name "unconnected-(U201B-NC_36-PadD13)") (class "Default")
      (node (ref "U201") (pin "D13") (pinfunction "NC_36_D13") (pintype "passive+no_connect"))
    )
    (net (code "68") (name "unconnected-(U201B-NC_37-PadD14)") (class "Default")
      (node (ref "U201") (pin "D14") (pinfunction "NC_37_D14") (pintype "passive+no_connect"))
    )
    (net (code "69") (name "unconnected-(U201B-NC_38-PadE1)") (class "Default")
      (node (ref "U201") (pin "E1") (pinfunction "NC_38_E1") (pintype "passive+no_connect"))
    )
    (net (code "70") (name "unconnected-(U201B-NC_39-PadE2)") (class "Default")
      (node (ref "U201") (pin "E2") (pinfunction "NC_39_E2") (pintype "passive+no_connect"))
    )
    (net (code "71") (name "unconnected-(U201B-NC_40-PadE3)") (class "Default")
      (node (ref "U201") (pin "E3") (pinfunction "NC_40_E3") (pintype "passive+no_connect"))
    )
    (net (code "72") (name "unconnected-(U201B-NC_41-PadE5)") (class "Default")
      (node (ref "U201") (pin "E5") (pinfunction "NC_41_E5") (pintype "passive+no_connect"))
    )
    (net (code "73") (name "unconnected-(U201B-NC_42-PadE8)") (class "Default")
      (node (ref "U201") (pin "E8") (pinfunction "NC_42_E8") (pintype "passive+no_connect"))
    )
    (net (code "74") (name "unconnected-(U201B-NC_43-PadE9)") (class "Default")
      (node (ref "U201") (pin "E9") (pinfunction "NC_43_E9") (pintype "passive+no_connect"))
    )
    (net (code "75") (name "unconnected-(U201B-NC_44-PadE10)") (class "Default")
      (node (ref "U201") (pin "E10") (pinfunction "NC_44_E10") (pintype "passive+no_connect"))
    )
    (net (code "76") (name "unconnected-(U201B-NC_45-PadE12)") (class "Default")
      (node (ref "U201") (pin "E12") (pinfunction "NC_45_E12") (pintype "passive+no_connect"))
    )
    (net (code "77") (name "unconnected-(U201B-NC_46-PadE13)") (class "Default")
      (node (ref "U201") (pin "E13") (pinfunction "NC_46_E13") (pintype "passive+no_connect"))
    )
    (net (code "78") (name "unconnected-(U201B-NC_47-PadE14)") (class "Default")
      (node (ref "U201") (pin "E14") (pinfunction "NC_47_E14") (pintype "passive+no_connect"))
    )
    (net (code "79") (name "unconnected-(U201B-NC_48-PadF1)") (class "Default")
      (node (ref "U201") (pin "F1") (pinfunction "NC_48_F1") (pintype "passive+no_connect"))
    )
    (net (code "80") (name "unconnected-(U201B-NC_49-PadF2)") (class "Default")
      (node (ref "U201") (pin "F2") (pinfunction "NC_49_F2") (pintype "passive+no_connect"))
    )
    (net (code "81") (name "unconnected-(U201B-NC_50-PadF3)") (class "Default")
      (node (ref "U201") (pin "F3") (pinfunction "NC_50_F3") (pintype "passive+no_connect"))
    )
    (net (code "82") (name "unconnected-(U201B-NC_51-PadF10)") (class "Default")
      (node (ref "U201") (pin "F10") (pinfunction "NC_51_F10") (pintype "passive+no_connect"))
    )
    (net (code "83") (name "unconnected-(U201B-NC_52-PadF12)") (class "Default")
      (node (ref "U201") (pin "F12") (pinfunction "NC_52_F12") (pintype "passive+no_connect"))
    )
    (net (code "84") (name "unconnected-(U201B-NC_53-PadF13)") (class "Default")
      (node (ref "U201") (pin "F13") (pinfunction "NC_53_F13") (pintype "passive+no_connect"))
    )
    (net (code "85") (name "unconnected-(U201B-NC_54-PadF14)") (class "Default")
      (node (ref "U201") (pin "F14") (pinfunction "NC_54_F14") (pintype "passive+no_connect"))
    )
    (net (code "86") (name "unconnected-(U201B-NC_55-PadG1)") (class "Default")
      (node (ref "U201") (pin "G1") (pinfunction "NC_55_G1") (pintype "passive+no_connect"))
    )
    (net (code "87") (name "unconnected-(U201B-NC_56-PadG2)") (class "Default")
      (node (ref "U201") (pin "G2") (pinfunction "NC_56_G2") (pintype "passive+no_connect"))
    )
    (net (code "88") (name "unconnected-(U201B-NC_57-PadG3)") (class "Default")
      (node (ref "U201") (pin "G3") (pinfunction "NC_57_G3") (pintype "passive+no_connect"))
    )
    (net (code "89") (name "unconnected-(U201B-NC_58-PadG10)") (class "Default")
      (node (ref "U201") (pin "G10") (pinfunction "NC_58_G10") (pintype "passive+no_connect"))
    )
    (net (code "90") (name "unconnected-(U201B-NC_59-PadG12)") (class "Default")
      (node (ref "U201") (pin "G12") (pinfunction "NC_59_G12") (pintype "passive+no_connect"))
    )
    (net (code "91") (name "unconnected-(U201B-NC_60-PadG13)") (class "Default")
      (node (ref "U201") (pin "G13") (pinfunction "NC_60_G13") (pintype "passive+no_connect"))
    )
    (net (code "92") (name "unconnected-(U201B-NC_61-PadG14)") (class "Default")
      (node (ref "U201") (pin "G14") (pinfunction "NC_61_G14") (pintype "passive+no_connect"))
    )
    (net (code "93") (name "unconnected-(U201B-NC_62-PadH1)") (class "Default")
      (node (ref "U201") (pin "H1") (pinfunction "NC_62_H1") (pintype "passive+no_connect"))
    )
    (net (code "94") (name "unconnected-(U201B-NC_63-PadH2)") (class "Default")
      (node (ref "U201") (pin "H2") (pinfunction "NC_63_H2") (pintype "passive+no_connect"))
    )
    (net (code "95") (name "unconnected-(U201B-NC_64-PadH3)") (class "Default")
      (node (ref "U201") (pin "H3") (pinfunction "NC_64_H3") (pintype "passive+no_connect"))
    )
    (net (code "96") (name "unconnected-(U201B-NC_65-PadH12)") (class "Default")
      (node (ref "U201") (pin "H12") (pinfunction "NC_65_H12") (pintype "passive+no_connect"))
    )
    (net (code "97") (name "unconnected-(U201B-NC_66-PadH13)") (class "Default")
      (node (ref "U201") (pin "H13") (pinfunction "NC_66_H13") (pintype "passive+no_connect"))
    )
    (net (code "98") (name "unconnected-(U201B-NC_67-PadH14)") (class "Default")
      (node (ref "U201") (pin "H14") (pinfunction "NC_67_H14") (pintype "passive+no_connect"))
    )
    (net (code "99") (name "unconnected-(U201B-NC_68-PadJ1)") (class "Default")
      (node (ref "U201") (pin "J1") (pinfunction "NC_68_J1") (pintype "passive+no_connect"))
    )
    (net (code "100") (name "unconnected-(U201B-NC_69-PadJ2)") (class "Default")
      (node (ref "U201") (pin "J2") (pinfunction "NC_69_J2") (pintype "passive+no_connect"))
    )
    (net (code "101") (name "unconnected-(U201B-NC_70-PadJ3)") (class "Default")
      (node (ref "U201") (pin "J3") (pinfunction "NC_70_J3") (pintype "passive+no_connect"))
    )
    (net (code "102") (name "unconnected-(U201B-NC_71-PadJ12)") (class "Default")
      (node (ref "U201") (pin "J12") (pinfunction "NC_71_J12") (pintype "passive+no_connect"))
    )
    (net (code "103") (name "unconnected-(U201B-NC_72-PadJ13)") (class "Default")
      (node (ref "U201") (pin "J13") (pinfunction "NC_72_J13") (pintype "passive+no_connect"))
    )
    (net (code "104") (name "unconnected-(U201B-NC_73-PadJ14)") (class "Default")
      (node (ref "U201") (pin "J14") (pinfunction "NC_73_J14") (pintype "passive+no_connect"))
    )
    (net (code "105") (name "unconnected-(U201B-NC_74-PadK1)") (class "Default")
      (node (ref "U201") (pin "K1") (pinfunction "NC_74_K1") (pintype "passive+no_connect"))
    )
    (net (code "106") (name "unconnected-(U201B-NC_75-PadK2)") (class "Default")
      (node (ref "U201") (pin "K2") (pinfunction "NC_75_K2") (pintype "passive+no_connect"))
    )
    (net (code "107") (name "unconnected-(U201B-NC_76-PadK3)") (class "Default")
      (node (ref "U201") (pin "K3") (pinfunction "NC_76_K3") (pintype "passive+no_connect"))
    )
    (net (code "108") (name "unconnected-(U201B-NC_77-PadK6)") (class "Default")
      (node (ref "U201") (pin "K6") (pinfunction "NC_77_K6") (pintype "passive+no_connect"))
    )
    (net (code "109") (name "unconnected-(U201B-NC_78-PadK7)") (class "Default")
      (node (ref "U201") (pin "K7") (pinfunction "NC_78_K7") (pintype "passive+no_connect"))
    )
    (net (code "110") (name "unconnected-(U201B-NC_79-PadK10)") (class "Default")
      (node (ref "U201") (pin "K10") (pinfunction "NC_79_K10") (pintype "passive+no_connect"))
    )
    (net (code "111") (name "unconnected-(U201B-NC_80-PadK12)") (class "Default")
      (node (ref "U201") (pin "K12") (pinfunction "NC_80_K12") (pintype "passive+no_connect"))
    )
    (net (code "112") (name "unconnected-(U201B-NC_81-PadK13)") (class "Default")
      (node (ref "U201") (pin "K13") (pinfunction "NC_81_K13") (pintype "passive+no_connect"))
    )
    (net (code "113") (name "unconnected-(U201B-NC_82-PadK14)") (class "Default")
      (node (ref "U201") (pin "K14") (pinfunction "NC_82_K14") (pintype "passive+no_connect"))
    )
    (net (code "114") (name "unconnected-(U201B-NC_83-PadL1)") (class "Default")
      (node (ref "U201") (pin "L1") (pinfunction "NC_83_L1") (pintype "passive+no_connect"))
    )
    (net (code "115") (name "unconnected-(U201B-NC_84-PadL2)") (class "Default")
      (node (ref "U201") (pin "L2") (pinfunction "NC_84_L2") (pintype "passive+no_connect"))
    )
    (net (code "116") (name "unconnected-(U201B-NC_85-PadL3)") (class "Default")
      (node (ref "U201") (pin "L3") (pinfunction "NC_85_L3") (pintype "passive+no_connect"))
    )
    (net (code "117") (name "unconnected-(U201B-NC_86-PadL12)") (class "Default")
      (node (ref "U201") (pin "L12") (pinfunction "NC_86_L12") (pintype "passive+no_connect"))
    )
    (net (code "118") (name "unconnected-(U201B-NC_87-PadL13)") (class "Default")
      (node (ref "U201") (pin "L13") (pinfunction "NC_87_L13") (pintype "passive+no_connect"))
    )
    (net (code "119") (name "unconnected-(U201B-NC_88-PadL14)") (class "Default")
      (node (ref "U201") (pin "L14") (pinfunction "NC_88_L14") (pintype "passive+no_connect"))
    )
    (net (code "120") (name "unconnected-(U201B-NC_89-PadM1)") (class "Default")
      (node (ref "U201") (pin "M1") (pinfunction "NC_89_M1") (pintype "passive+no_connect"))
    )
    (net (code "121") (name "unconnected-(U201B-NC_90-PadM2)") (class "Default")
      (node (ref "U201") (pin "M2") (pinfunction "NC_90_M2") (pintype "passive+no_connect"))
    )
    (net (code "122") (name "unconnected-(U201B-NC_91-PadM3)") (class "Default")
      (node (ref "U201") (pin "M3") (pinfunction "NC_91_M3") (pintype "passive+no_connect"))
    )
    (net (code "123") (name "unconnected-(U201B-NC_92-PadM7)") (class "Default")
      (node (ref "U201") (pin "M7") (pinfunction "NC_92_M7") (pintype "passive+no_connect"))
    )
    (net (code "124") (name "unconnected-(U201B-NC_93-PadM8)") (class "Default")
      (node (ref "U201") (pin "M8") (pinfunction "NC_93_M8") (pintype "passive+no_connect"))
    )
    (net (code "125") (name "unconnected-(U201B-NC_94-PadM9)") (class "Default")
      (node (ref "U201") (pin "M9") (pinfunction "NC_94_M9") (pintype "passive+no_connect"))
    )
    (net (code "126") (name "unconnected-(U201B-NC_95-PadM10)") (class "Default")
      (node (ref "U201") (pin "M10") (pinfunction "NC_95_M10") (pintype "passive+no_connect"))
    )
    (net (code "127") (name "unconnected-(U201B-NC_96-PadM11)") (class "Default")
      (node (ref "U201") (pin "M11") (pinfunction "NC_96_M11") (pintype "passive+no_connect"))
    )
    (net (code "128") (name "unconnected-(U201B-NC_97-PadM12)") (class "Default")
      (node (ref "U201") (pin "M12") (pinfunction "NC_97_M12") (pintype "passive+no_connect"))
    )
    (net (code "129") (name "unconnected-(U201B-NC_98-PadM13)") (class "Default")
      (node (ref "U201") (pin "M13") (pinfunction "NC_98_M13") (pintype "passive+no_connect"))
    )
    (net (code "130") (name "unconnected-(U201B-NC_99-PadM14)") (class "Default")
      (node (ref "U201") (pin "M14") (pinfunction "NC_99_M14") (pintype "passive+no_connect"))
    )
    (net (code "131") (name "unconnected-(U201B-NC_100-PadN1)") (class "Default")
      (node (ref "U201") (pin "N1") (pinfunction "NC_100_N1") (pintype "passive+no_connect"))
    )
    (net (code "132") (name "unconnected-(U201B-NC_101-PadN3)") (class "Default")
      (node (ref "U201") (pin "N3") (pinfunction "NC_101_N3") (pintype "passive+no_connect"))
    )
    (net (code "133") (name "unconnected-(U201B-NC_102-PadN6)") (class "Default")
      (node (ref "U201") (pin "N6") (pinfunction "NC_102_N6") (pintype "passive+no_connect"))
    )
    (net (code "134") (name "unconnected-(U201B-NC_103-PadN7)") (class "Default")
      (node (ref "U201") (pin "N7") (pinfunction "NC_103_N7") (pintype "passive+no_connect"))
    )
    (net (code "135") (name "unconnected-(U201B-NC_104-PadN8)") (class "Default")
      (node (ref "U201") (pin "N8") (pinfunction "NC_104_N8") (pintype "passive+no_connect"))
    )
    (net (code "136") (name "unconnected-(U201B-NC_105-PadN9)") (class "Default")
      (node (ref "U201") (pin "N9") (pinfunction "NC_105_N9") (pintype "passive+no_connect"))
    )
    (net (code "137") (name "unconnected-(U201B-NC_106-PadN10)") (class "Default")
      (node (ref "U201") (pin "N10") (pinfunction "NC_106_N10") (pintype "passive+no_connect"))
    )
    (net (code "138") (name "unconnected-(U201B-NC_107-PadN11)") (class "Default")
      (node (ref "U201") (pin "N11") (pinfunction "NC_107_N11") (pintype "passive+no_connect"))
    )
    (net (code "139") (name "unconnected-(U201B-NC_108-PadN12)") (class "Default")
      (node (ref "U201") (pin "N12") (pinfunction "NC_108_N12") (pintype "passive+no_connect"))
    )
    (net (code "140") (name "unconnected-(U201B-NC_109-PadN13)") (class "Default")
      (node (ref "U201") (pin "N13") (pinfunction "NC_109_N13") (pintype "passive+no_connect"))
    )
    (net (code "141") (name "unconnected-(U201B-NC_110-PadN14)") (class "Default")
      (node (ref "U201") (pin "N14") (pinfunction "NC_110_N14") (pintype "passive+no_connect"))
    )
    (net (code "142") (name "unconnected-(U201B-NC_111-PadP1)") (class "Default")
      (node (ref "U201") (pin "P1") (pinfunction "NC_111_P1") (pintype "passive+no_connect"))
    )
    (net (code "143") (name "unconnected-(U201B-NC_112-PadP2)") (class "Default")
      (node (ref "U201") (pin "P2") (pinfunction "NC_112_P2") (pintype "passive+no_connect"))
    )
    (net (code "144") (name "unconnected-(U201B-NC_113-PadP7)") (class "Default")
      (node (ref "U201") (pin "P7") (pinfunction "NC_113_P7") (pintype "passive+no_connect"))
    )
    (net (code "145") (name "unconnected-(U201B-NC_114-PadP8)") (class "Default")
      (node (ref "U201") (pin "P8") (pinfunction "NC_114_P8") (pintype "passive+no_connect"))
    )
    (net (code "146") (name "unconnected-(U201B-NC_115-PadP9)") (class "Default")
      (node (ref "U201") (pin "P9") (pinfunction "NC_115_P9") (pintype "passive+no_connect"))
    )
    (net (code "147") (name "unconnected-(U201B-NC_116-PadP10)") (class "Default")
      (node (ref "U201") (pin "P10") (pinfunction "NC_116_P10") (pintype "passive+no_connect"))
    )
    (net (code "148") (name "unconnected-(U201B-NC_117-PadP11)") (class "Default")
      (node (ref "U201") (pin "P11") (pinfunction "NC_117_P11") (pintype "passive+no_connect"))
    )
    (net (code "149") (name "unconnected-(U201B-NC_118-PadP12)") (class "Default")
      (node (ref "U201") (pin "P12") (pinfunction "NC_118_P12") (pintype "passive+no_connect"))
    )
    (net (code "150") (name "unconnected-(U201B-NC_119-PadP13)") (class "Default")
      (node (ref "U201") (pin "P13") (pinfunction "NC_119_P13") (pintype "passive+no_connect"))
    )
    (net (code "151") (name "unconnected-(U201B-NC_120-PadP14)") (class "Default")
      (node (ref "U201") (pin "P14") (pinfunction "NC_120_P14") (pintype "passive+no_connect"))
    )
    (net (code "152") (name "unconnected-(U202-CT-Pad4)") (class "Default")
      (node (ref "U202") (pin "4") (pinfunction "CT_4") (pintype "passive+no_connect"))
    )
  )
)
